# Sheet_1.net
KiCad netlist of a schematic drawn in Altium Designer
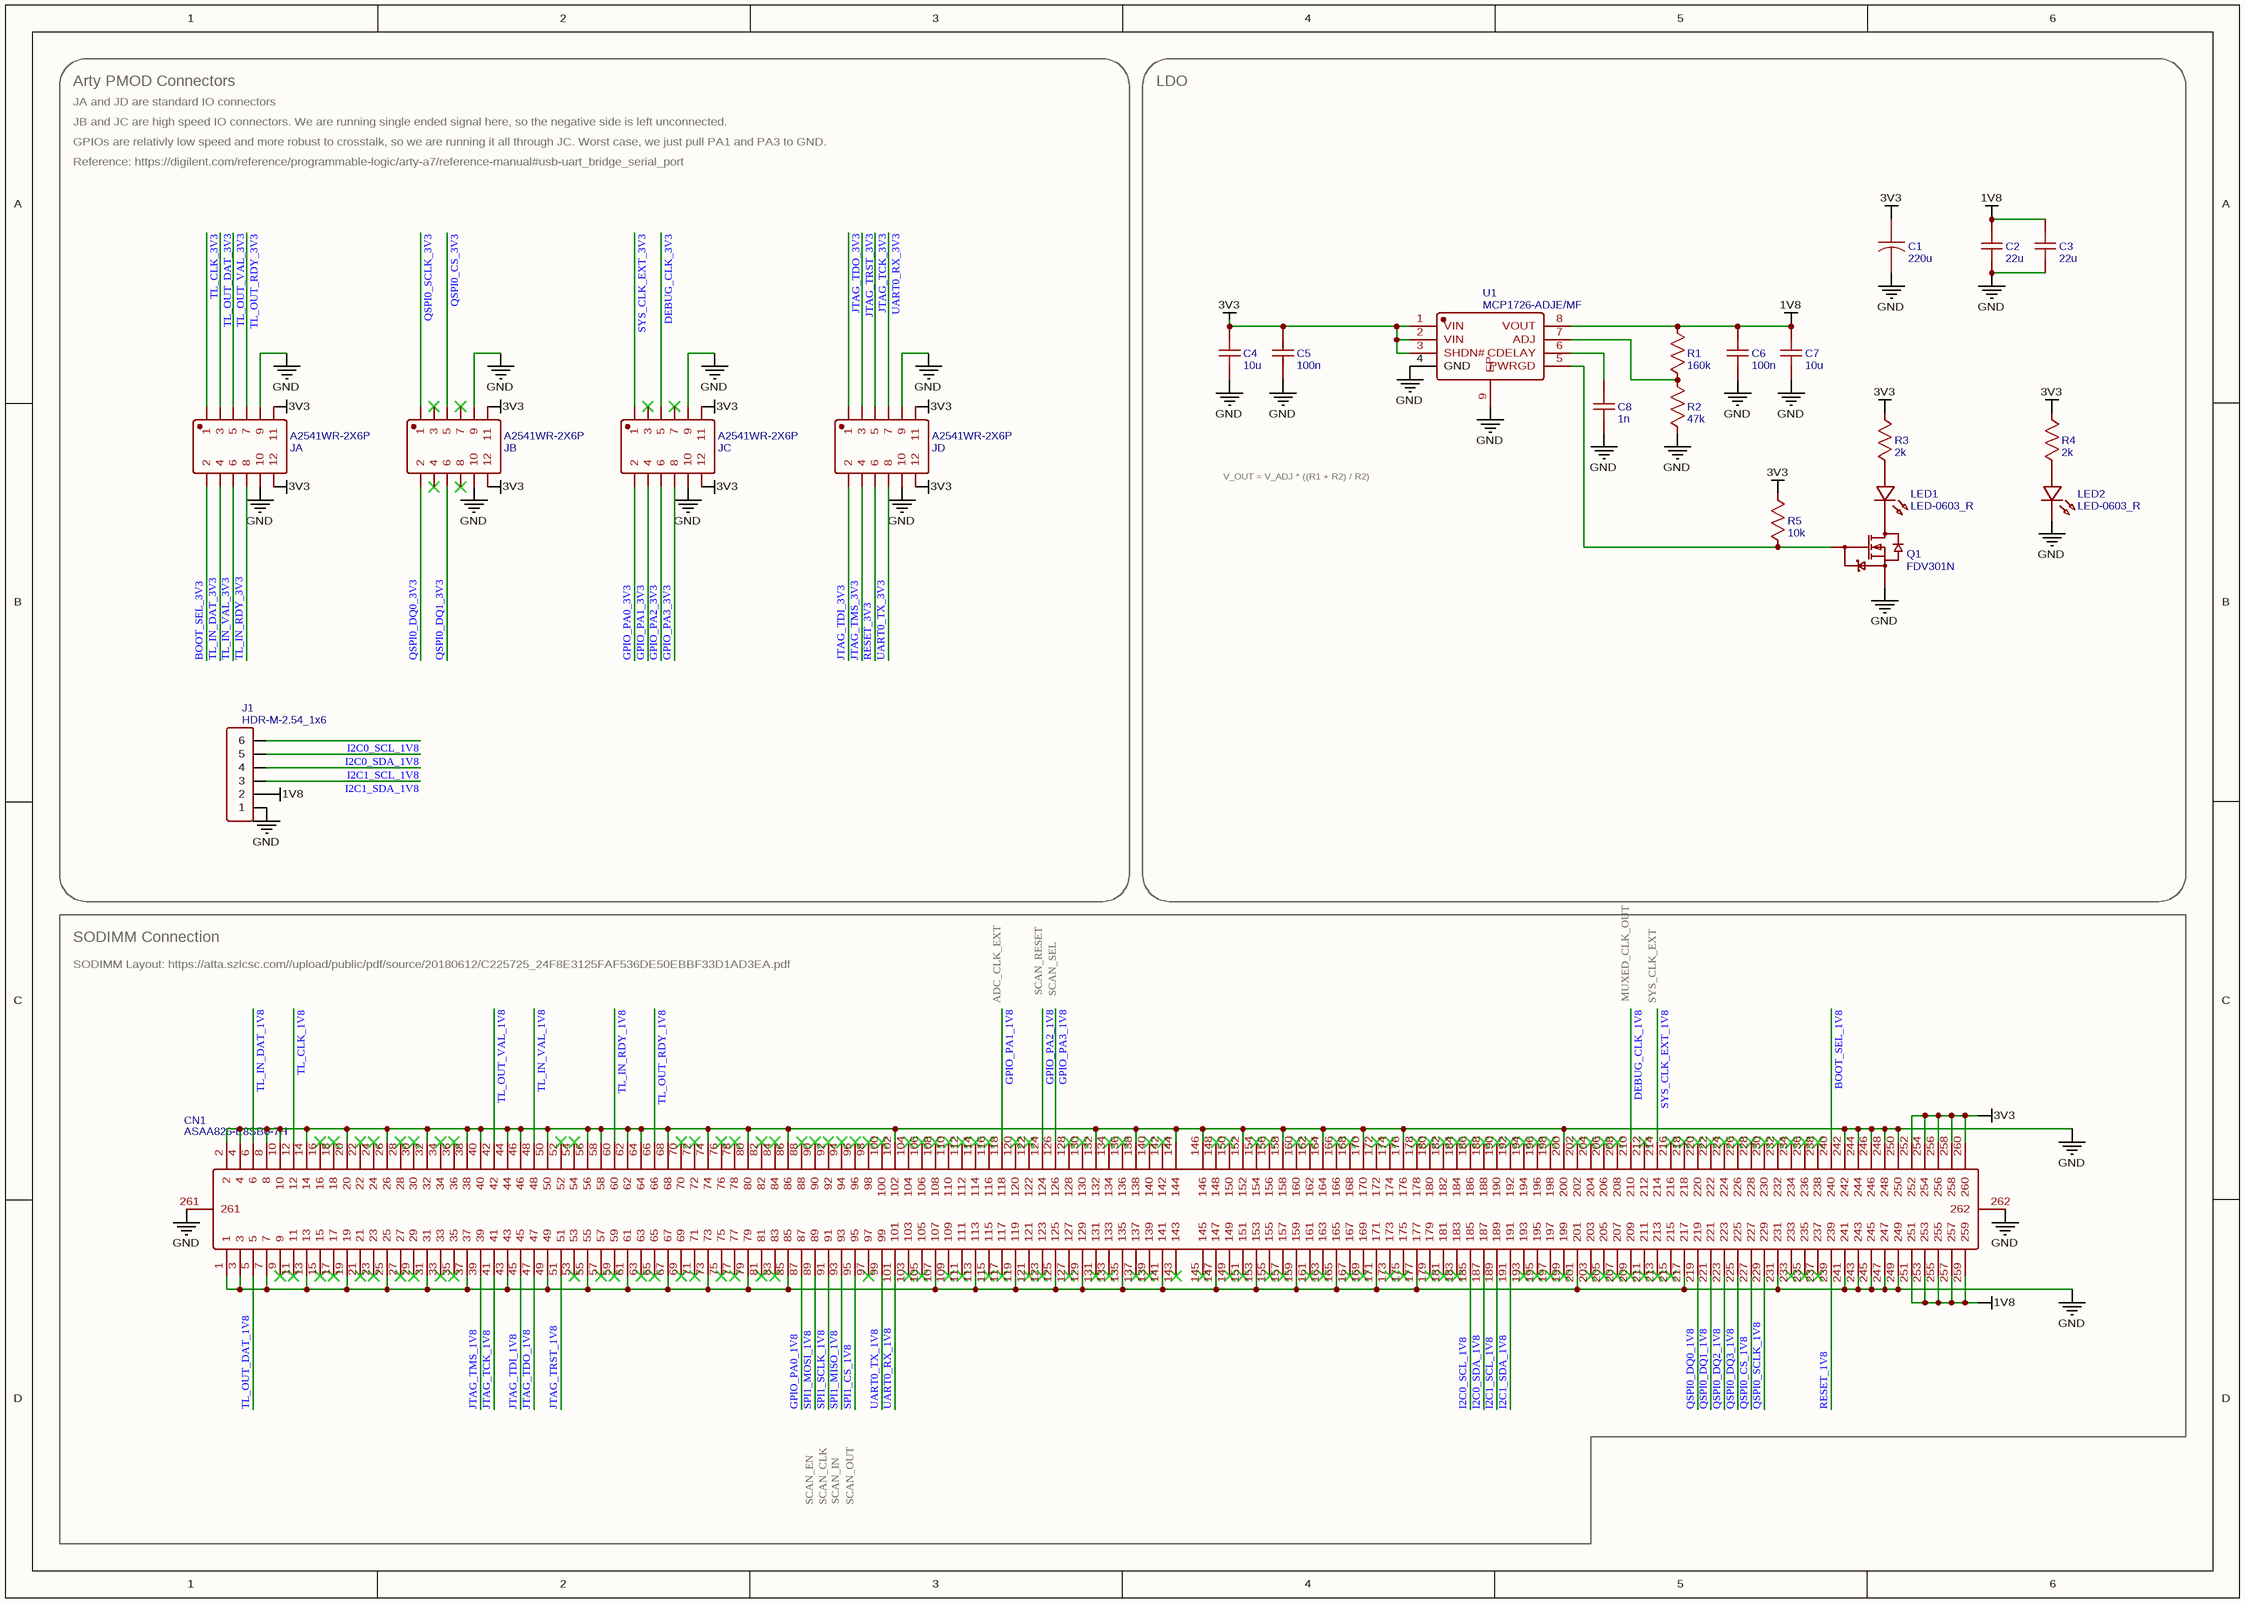
[diagram p0: Sheet_1.schdoc]

(export (version "E")
  (design (tool "Eeschema 10.0.6"))
  (components
    (comp (ref "C1")
      (value "220u")
      (footprint "CAPPR5.0-D6.3_L6.6_W6.6")
      (fields
        (field (name "BOM_SUPPLIER PART") "C131157")
        (field (name "BOM_MANUFACTURER PART") "CK1A221M-CRE54")
      )
      (libsource (lib "altium-import") (part "root_3_220u_"))
    )
    (comp (ref "C2")
      (value "22u")
      (footprint "CAPA-1206")
      (fields
        (field (name "BOM_SUPPLIER PART") "C12891")
        (field (name "BOM_MANUFACTURER PART") "CL31A226KAHNNNE")
      )
      (libsource (lib "altium-import") (part "root_1_22u_"))
    )
    (comp (ref "C3")
      (value "22u")
      (footprint "CAPA-1206")
      (fields
        (field (name "BOM_SUPPLIER PART") "C12891")
        (field (name "BOM_MANUFACTURER PART") "CL31A226KAHNNNE")
      )
      (libsource (lib "altium-import") (part "root_1_22u_"))
    )
    (comp (ref "C4")
      (value "10u")
      (footprint "CAPA-0402")
      (fields
        (field (name "BOM_SUPPLIER PART") "C87148")
        (field (name "BOM_MANUFACTURER PART") "JMK105CBJ106MV-F")
      )
      (libsource (lib "altium-import") (part "root_1_10u_"))
    )
    (comp (ref "C5")
      (value "100n")
      (footprint "CAPA-0402")
      (fields
        (field (name "BOM_SUPPLIER PART") "C307331")
        (field (name "BOM_MANUFACTURER PART") "CL05B104KB54PNC")
      )
      (libsource (lib "altium-import") (part "root_1_100n_"))
    )
    (comp (ref "C6")
      (value "100n")
      (footprint "CAPA-0402")
      (fields
        (field (name "BOM_SUPPLIER PART") "C307331")
        (field (name "BOM_MANUFACTURER PART") "CL05B104KB54PNC")
      )
      (libsource (lib "altium-import") (part "root_1_100n_"))
    )
    (comp (ref "C7")
      (value "10u")
      (footprint "CAPA-0402")
      (fields
        (field (name "BOM_SUPPLIER PART") "C87148")
        (field (name "BOM_MANUFACTURER PART") "JMK105CBJ106MV-F")
      )
      (libsource (lib "altium-import") (part "root_1_10u_"))
    )
    (comp (ref "C8")
      (value "1n")
      (footprint "CAPA-0402")
      (fields
        (field (name "BOM_SUPPLIER PART") "C113780")
        (field (name "BOM_MANUFACTURER PART") "CC0402JRNPO9BN102")
      )
      (libsource (lib "altium-import") (part "root_1_1n_"))
    )
    (comp (ref "CN1")
      (value "ASAA826-E8SB0-7H")
      (footprint "CONN-SMD_ASAA826-E8SB0-7H")
      (fields (field (name "BOM_SUPPLIER PART") "C2761395"))
      (libsource (lib "altium-import") (part "root_0_ASAA826-E8SB0-7H_"))
    )
    (comp (ref "J1")
      (value "HDR-M-2.54_1x6")
      (footprint "HDR-M-2.54_1X6")
      (fields (field (name "BOM_SUPPLIER PART") "C190819") (field (name "CONTRIBUTOR") "LCEDA_Lib"))
      (libsource (lib "altium-import") (part "root_2_HDR-M-2.54_1x6_"))
    )
    (comp (ref "JA")
      (value "A2541WR-2X6P")
      (footprint "CONN-TH_A2541WR-2X6P")
      (fields
        (field (name "BOM_SUPPLIER PART") "C239337")
        (field (name "BOM_MANUFACTURER PART") "A2541WR-2x6P")
      )
      (libsource (lib "altium-import") (part "root_1_A2541WR-2X6P_"))
    )
    (comp (ref "JB")
      (value "A2541WR-2X6P")
      (footprint "CONN-TH_A2541WR-2X6P")
      (fields
        (field (name "BOM_SUPPLIER PART") "C239337")
        (field (name "BOM_MANUFACTURER PART") "A2541WR-2x6P")
      )
      (libsource (lib "altium-import") (part "root_1_A2541WR-2X6P_"))
    )
    (comp (ref "JC")
      (value "A2541WR-2X6P")
      (footprint "CONN-TH_A2541WR-2X6P")
      (fields
        (field (name "BOM_SUPPLIER PART") "C239337")
        (field (name "BOM_MANUFACTURER PART") "A2541WR-2x6P")
      )
      (libsource (lib "altium-import") (part "root_1_A2541WR-2X6P_"))
    )
    (comp (ref "JD")
      (value "A2541WR-2X6P")
      (footprint "CONN-TH_A2541WR-2X6P")
      (fields
        (field (name "BOM_SUPPLIER PART") "C239337")
        (field (name "BOM_MANUFACTURER PART") "A2541WR-2x6P")
      )
      (libsource (lib "altium-import") (part "root_1_A2541WR-2X6P_"))
    )
    (comp (ref "LED1")
      (value "LED-0603_R")
      (footprint "LED-0603")
      (fields
        (field (name "BOM_MANUFACTURER PART") "19-217/R6C-AL1M2VY/3T")
        (field (name "BOM_SUPPLIER PART") "C72044")
        (field (name "CONTRIBUTOR") "LCEDA_01")
      )
      (libsource (lib "altium-import") (part "root_3_LED-0603_R_"))
    )
    (comp (ref "LED2")
      (value "LED-0603_R")
      (footprint "LED-0603")
      (fields
        (field (name "BOM_MANUFACTURER PART") "19-217/R6C-AL1M2VY/3T")
        (field (name "BOM_SUPPLIER PART") "C72044")
        (field (name "CONTRIBUTOR") "LCEDA_01")
      )
      (libsource (lib "altium-import") (part "root_3_LED-0603_R_"))
    )
    (comp (ref "Q1")
      (value "FDV301N")
      (footprint "SOT-23_L2.9-W1.3-P1.90-LS2.4-BR")
      (fields (field (name "BOM_SUPPLIER PART") "C15310"))
      (libsource (lib "altium-import") (part "root_0_FDV301N_"))
    )
    (comp (ref "R1")
      (value "160k")
      (footprint "RES-0402")
      (fields
        (field (name "BOM_SUPPLIER PART") "C25757")
        (field (name "BOM_MANUFACTURER PART") "0402WGF1603TCE")
      )
      (libsource (lib "altium-import") (part "root_1_160k_"))
    )
    (comp (ref "R2")
      (value "47k")
      (footprint "RES-0402")
      (fields
        (field (name "BOM_SUPPLIER PART") "C25792")
        (field (name "BOM_MANUFACTURER PART") "0402WGF4702TCE")
      )
      (libsource (lib "altium-import") (part "root_1_47k_"))
    )
    (comp (ref "R3")
      (value "2k")
      (footprint "RES-0402")
      (fields
        (field (name "BOM_SUPPLIER PART") "C4109")
        (field (name "BOM_MANUFACTURER PART") "0402WGF2001TCE")
      )
      (libsource (lib "altium-import") (part "root_1_2k_"))
    )
    (comp (ref "R4")
      (value "2k")
      (footprint "RES-0402")
      (fields
        (field (name "BOM_SUPPLIER PART") "C4109")
        (field (name "BOM_MANUFACTURER PART") "0402WGF2001TCE")
      )
      (libsource (lib "altium-import") (part "root_1_2k_"))
    )
    (comp (ref "R5")
      (value "10k")
      (footprint "RES-0402")
      (fields
        (field (name "BOM_SUPPLIER PART") "C25744")
        (field (name "BOM_MANUFACTURER PART") "0402WGF1002TCE")
      )
      (libsource (lib "altium-import") (part "root_1_10k_"))
    )
    (comp (ref "U1")
      (value "MCP1726-ADJE/MF")
      (footprint "TDFN-8_L3.0-W3.0-P0.65-BL-EP")
      (fields (field (name "BOM_SUPPLIER PART") "C184287"))
      (libsource (lib "altium-import") (part "root_0_MCP1726-ADJE/MF_"))
    )
  )
  (nets
    (net (code "1") (name "/BOOT_SEL_1V8") (class "Default")
      (node (ref "CN1") (pin "240") (pinfunction "240_240") (pintype "passive"))
    )
    (net (code "2") (name "/BOOT_SEL_3V3") (class "Default")
      (node (ref "JA") (pin "2") (pinfunction "2_2") (pintype "passive"))
    )
    (net (code "3") (name "/DEBUG_CLK_1V8") (class "Default")
      (node (ref "CN1") (pin "210") (pinfunction "210_210") (pintype "passive"))
    )
    (net (code "4") (name "/DEBUG_CLK_3V3") (class "Default")
      (node (ref "JC") (pin "5") (pinfunction "5_5") (pintype "passive"))
    )
    (net (code "5") (name "/GPIO_PA0_1V8") (class "Default")
      (node (ref "CN1") (pin "87") (pinfunction "87_87") (pintype "passive"))
    )
    (net (code "6") (name "/GPIO_PA0_3V3") (class "Default")
      (node (ref "JC") (pin "2") (pinfunction "2_2") (pintype "passive"))
    )
    (net (code "7") (name "/GPIO_PA1_1V8") (class "Default")
      (node (ref "CN1") (pin "118") (pinfunction "118_118") (pintype "passive"))
    )
    (net (code "8") (name "/GPIO_PA1_3V3") (class "Default")
      (node (ref "JC") (pin "4") (pinfunction "4_4") (pintype "passive"))
    )
    (net (code "9") (name "/GPIO_PA2_1V8") (class "Default")
      (node (ref "CN1") (pin "124") (pinfunction "124_124") (pintype "passive"))
    )
    (net (code "10") (name "/GPIO_PA2_3V3") (class "Default")
      (node (ref "JC") (pin "6") (pinfunction "6_6") (pintype "passive"))
    )
    (net (code "11") (name "/GPIO_PA3_1V8") (class "Default")
      (node (ref "CN1") (pin "126") (pinfunction "126_126") (pintype "passive"))
    )
    (net (code "12") (name "/GPIO_PA3_3V3") (class "Default")
      (node (ref "JC") (pin "8") (pinfunction "8_8") (pintype "passive"))
    )
    (net (code "13") (name "/I2C0_SCL_1V8") (class "Default")
      (node (ref "CN1") (pin "185") (pinfunction "185_185") (pintype "passive"))
      (node (ref "J1") (pin "6") (pinfunction "6_6") (pintype "passive"))
    )
    (net (code "14") (name "/I2C0_SDA_1V8") (class "Default")
      (node (ref "CN1") (pin "187") (pinfunction "187_187") (pintype "passive"))
      (node (ref "J1") (pin "5") (pinfunction "5_5") (pintype "passive"))
    )
    (net (code "15") (name "/I2C1_SCL_1V8") (class "Default")
      (node (ref "CN1") (pin "189") (pinfunction "189_189") (pintype "passive"))
      (node (ref "J1") (pin "4") (pinfunction "4_4") (pintype "passive"))
    )
    (net (code "16") (name "/I2C1_SDA_1V8") (class "Default")
      (node (ref "CN1") (pin "191") (pinfunction "191_191") (pintype "passive"))
      (node (ref "J1") (pin "3") (pinfunction "3_3") (pintype "passive"))
    )
    (net (code "17") (name "/JTAG_TCK_1V8") (class "Default")
      (node (ref "CN1") (pin "41") (pinfunction "41_41") (pintype "passive"))
    )
    (net (code "18") (name "/JTAG_TCK_3V3") (class "Default")
      (node (ref "JD") (pin "5") (pinfunction "5_5") (pintype "passive"))
    )
    (net (code "19") (name "/JTAG_TDI_1V8") (class "Default")
      (node (ref "CN1") (pin "45") (pinfunction "45_45") (pintype "passive"))
    )
    (net (code "20") (name "/JTAG_TDI_3V3") (class "Default")
      (node (ref "JD") (pin "2") (pinfunction "2_2") (pintype "passive"))
    )
    (net (code "21") (name "/JTAG_TDO_1V8") (class "Default")
      (node (ref "CN1") (pin "47") (pinfunction "47_47") (pintype "passive"))
    )
    (net (code "22") (name "/JTAG_TDO_3V3") (class "Default")
      (node (ref "JD") (pin "1") (pinfunction "1_1") (pintype "passive"))
    )
    (net (code "23") (name "/JTAG_TMS_1V8") (class "Default")
      (node (ref "CN1") (pin "39") (pinfunction "39_39") (pintype "passive"))
    )
    (net (code "24") (name "/JTAG_TMS_3V3") (class "Default")
      (node (ref "JD") (pin "4") (pinfunction "4_4") (pintype "passive"))
    )
    (net (code "25") (name "/JTAG_TRST_1V8") (class "Default")
      (node (ref "CN1") (pin "51") (pinfunction "51_51") (pintype "passive"))
    )
    (net (code "26") (name "/JTAG_TRST_3V3") (class "Default")
      (node (ref "JD") (pin "3") (pinfunction "3_3") (pintype "passive"))
    )
    (net (code "27") (name "/QSPI0_CS_1V8") (class "Default")
      (node (ref "CN1") (pin "227") (pinfunction "227_227") (pintype "passive"))
    )
    (net (code "28") (name "/QSPI0_CS_3V3") (class "Default")
      (node (ref "JB") (pin "5") (pinfunction "5_5") (pintype "passive"))
    )
    (net (code "29") (name "/QSPI0_DQ0_1V8") (class "Default")
      (node (ref "CN1") (pin "219") (pinfunction "219_219") (pintype "passive"))
    )
    (net (code "30") (name "/QSPI0_DQ0_3V3") (class "Default")
      (node (ref "JB") (pin "2") (pinfunction "2_2") (pintype "passive"))
    )
    (net (code "31") (name "/QSPI0_DQ1_1V8") (class "Default")
      (node (ref "CN1") (pin "221") (pinfunction "221_221") (pintype "passive"))
    )
    (net (code "32") (name "/QSPI0_DQ1_3V3") (class "Default")
      (node (ref "JB") (pin "6") (pinfunction "6_6") (pintype "passive"))
    )
    (net (code "33") (name "/QSPI0_DQ2_1V8") (class "Default")
      (node (ref "CN1") (pin "223") (pinfunction "223_223") (pintype "passive"))
    )
    (net (code "34") (name "/QSPI0_DQ3_1V8") (class "Default")
      (node (ref "CN1") (pin "225") (pinfunction "225_225") (pintype "passive"))
    )
    (net (code "35") (name "/QSPI0_SCLK_1V8") (class "Default")
      (node (ref "CN1") (pin "229") (pinfunction "229_229") (pintype "passive"))
    )
    (net (code "36") (name "/QSPI0_SCLK_3V3") (class "Default")
      (node (ref "JB") (pin "1") (pinfunction "1_1") (pintype "passive"))
    )
    (net (code "37") (name "/RESET_1V8") (class "Default")
      (node (ref "CN1") (pin "239") (pinfunction "239_239") (pintype "passive"))
    )
    (net (code "38") (name "/RESET_3V3") (class "Default")
      (node (ref "JD") (pin "6") (pinfunction "6_6") (pintype "passive"))
    )
    (net (code "39") (name "/SPI1_CS_1V8") (class "Default")
      (node (ref "CN1") (pin "95") (pinfunction "95_95") (pintype "passive"))
    )
    (net (code "40") (name "/SPI1_MISO_1V8") (class "Default")
      (node (ref "CN1") (pin "93") (pinfunction "93_93") (pintype "passive"))
    )
    (net (code "41") (name "/SPI1_MOSI_1V8") (class "Default")
      (node (ref "CN1") (pin "89") (pinfunction "89_89") (pintype "passive"))
    )
    (net (code "42") (name "/SPI1_SCLK_1V8") (class "Default")
      (node (ref "CN1") (pin "91") (pinfunction "91_91") (pintype "passive"))
    )
    (net (code "43") (name "/SYS_CLK_EXT_1V8") (class "Default")
      (node (ref "CN1") (pin "214") (pinfunction "214_214") (pintype "passive"))
    )
    (net (code "44") (name "/SYS_CLK_EXT_3V3") (class "Default")
      (node (ref "JC") (pin "1") (pinfunction "1_1") (pintype "passive"))
    )
    (net (code "45") (name "/TL_CLK_1V8") (class "Default")
      (node (ref "CN1") (pin "12") (pinfunction "12_12") (pintype "passive"))
    )
    (net (code "46") (name "/TL_CLK_3V3") (class "Default")
      (node (ref "JA") (pin "1") (pinfunction "1_1") (pintype "passive"))
    )
    (net (code "47") (name "/TL_IN_DAT_1V8") (class "Default")
      (node (ref "CN1") (pin "6") (pinfunction "6_6") (pintype "passive"))
    )
    (net (code "48") (name "/TL_IN_DAT_3V3") (class "Default")
      (node (ref "JA") (pin "4") (pinfunction "4_4") (pintype "passive"))
    )
    (net (code "49") (name "/TL_IN_RDY_1V8") (class "Default")
      (node (ref "CN1") (pin "60") (pinfunction "60_60") (pintype "passive"))
    )
    (net (code "50") (name "/TL_IN_RDY_3V3") (class "Default")
      (node (ref "JA") (pin "8") (pinfunction "8_8") (pintype "passive"))
    )
    (net (code "51") (name "/TL_IN_VAL_1V8") (class "Default")
      (node (ref "CN1") (pin "48") (pinfunction "48_48") (pintype "passive"))
    )
    (net (code "52") (name "/TL_IN_VAL_3V3") (class "Default")
      (node (ref "JA") (pin "6") (pinfunction "6_6") (pintype "passive"))
    )
    (net (code "53") (name "/TL_OUT_DAT_1V8") (class "Default")
      (node (ref "CN1") (pin "5") (pinfunction "5_5") (pintype "passive"))
    )
    (net (code "54") (name "/TL_OUT_DAT_3V3") (class "Default")
      (node (ref "JA") (pin "3") (pinfunction "3_3") (pintype "passive"))
    )
    (net (code "55") (name "/TL_OUT_RDY_1V8") (class "Default")
      (node (ref "CN1") (pin "66") (pinfunction "66_66") (pintype "passive"))
    )
    (net (code "56") (name "/TL_OUT_RDY_3V3") (class "Default")
      (node (ref "JA") (pin "7") (pinfunction "7_7") (pintype "passive"))
    )
    (net (code "57") (name "/TL_OUT_VAL_1V8") (class "Default")
      (node (ref "CN1") (pin "42") (pinfunction "42_42") (pintype "passive"))
    )
    (net (code "58") (name "/TL_OUT_VAL_3V3") (class "Default")
      (node (ref "JA") (pin "5") (pinfunction "5_5") (pintype "passive"))
    )
    (net (code "59") (name "/UART0_RX_1V8") (class "Default")
      (node (ref "CN1") (pin "101") (pinfunction "101_101") (pintype "passive"))
    )
    (net (code "60") (name "/UART0_RX_3V3") (class "Default")
      (node (ref "JD") (pin "7") (pinfunction "7_7") (pintype "passive"))
    )
    (net (code "61") (name "/UART0_TX_1V8") (class "Default")
      (node (ref "CN1") (pin "99") (pinfunction "99_99") (pintype "passive"))
    )
    (net (code "62") (name "/UART0_TX_3V3") (class "Default")
      (node (ref "JD") (pin "8") (pinfunction "8_8") (pintype "passive"))
    )
    (net (code "63") (name "1V8") (class "Default")
      (node (ref "C2") (pin "2") (pinfunction "2_2") (pintype "passive"))
      (node (ref "C3") (pin "2") (pinfunction "2_2") (pintype "passive"))
      (node (ref "C6") (pin "2") (pinfunction "2_2") (pintype "passive"))
      (node (ref "C7") (pin "2") (pinfunction "2_2") (pintype "passive"))
      (node (ref "CN1") (pin "251") (pinfunction "251_251") (pintype "passive"))
      (node (ref "CN1") (pin "253") (pinfunction "253_253") (pintype "passive"))
      (node (ref "CN1") (pin "255") (pinfunction "255_255") (pintype "passive"))
      (node (ref "CN1") (pin "257") (pinfunction "257_257") (pintype "passive"))
      (node (ref "CN1") (pin "259") (pinfunction "259_259") (pintype "passive"))
      (node (ref "J1") (pin "2") (pinfunction "2_2") (pintype "passive"))
      (node (ref "R1") (pin "2") (pinfunction "2_2") (pintype "passive"))
      (node (ref "U1") (pin "8") (pinfunction "VOUT_8") (pintype "passive"))
    )
    (net (code "64") (name "3V3") (class "Default")
      (node (ref "C1") (pin "1") (pinfunction "1_1") (pintype "passive"))
      (node (ref "C4") (pin "2") (pinfunction "2_2") (pintype "passive"))
      (node (ref "C5") (pin "2") (pinfunction "2_2") (pintype "passive"))
      (node (ref "CN1") (pin "252") (pinfunction "252_252") (pintype "passive"))
      (node (ref "CN1") (pin "254") (pinfunction "254_254") (pintype "passive"))
      (node (ref "CN1") (pin "256") (pinfunction "256_256") (pintype "passive"))
      (node (ref "CN1") (pin "258") (pinfunction "258_258") (pintype "passive"))
      (node (ref "CN1") (pin "260") (pinfunction "260_260") (pintype "passive"))
      (node (ref "JA") (pin "11") (pinfunction "11_11") (pintype "passive"))
      (node (ref "JA") (pin "12") (pinfunction "12_12") (pintype "passive"))
      (node (ref "JB") (pin "11") (pinfunction "11_11") (pintype "passive"))
      (node (ref "JB") (pin "12") (pinfunction "12_12") (pintype "passive"))
      (node (ref "JC") (pin "11") (pinfunction "11_11") (pintype "passive"))
      (node (ref "JC") (pin "12") (pinfunction "12_12") (pintype "passive"))
      (node (ref "JD") (pin "11") (pinfunction "11_11") (pintype "passive"))
      (node (ref "JD") (pin "12") (pinfunction "12_12") (pintype "passive"))
      (node (ref "R3") (pin "2") (pinfunction "2_2") (pintype "passive"))
      (node (ref "R4") (pin "2") (pinfunction "2_2") (pintype "passive"))
      (node (ref "R5") (pin "2") (pinfunction "2_2") (pintype "passive"))
      (node (ref "U1") (pin "1") (pinfunction "VIN_1") (pintype "passive"))
      (node (ref "U1") (pin "2") (pinfunction "VIN_2") (pintype "passive"))
      (node (ref "U1") (pin "3") (pinfunction "SHDN#_3") (pintype "passive"))
    )
    (net (code "65") (name "GND") (class "Default")
      (node (ref "C1") (pin "2") (pinfunction "2_2") (pintype "passive"))
      (node (ref "C2") (pin "1") (pinfunction "1_1") (pintype "passive"))
      (node (ref "C3") (pin "1") (pinfunction "1_1") (pintype "passive"))
      (node (ref "C4") (pin "1") (pinfunction "1_1") (pintype "passive"))
      (node (ref "C5") (pin "1") (pinfunction "1_1") (pintype "passive"))
      (node (ref "C6") (pin "1") (pinfunction "1_1") (pintype "passive"))
      (node (ref "C7") (pin "1") (pinfunction "1_1") (pintype "passive"))
      (node (ref "C8") (pin "1") (pinfunction "1_1") (pintype "passive"))
      (node (ref "CN1") (pin "1") (pinfunction "1_1") (pintype "passive"))
      (node (ref "CN1") (pin "10") (pinfunction "10_10") (pintype "passive"))
      (node (ref "CN1") (pin "102") (pinfunction "102_102") (pintype "passive"))
      (node (ref "CN1") (pin "107") (pinfunction "107_107") (pintype "passive"))
      (node (ref "CN1") (pin "113") (pinfunction "113_113") (pintype "passive"))
      (node (ref "CN1") (pin "119") (pinfunction "119_119") (pintype "passive"))
      (node (ref "CN1") (pin "125") (pinfunction "125_125") (pintype "passive"))
      (node (ref "CN1") (pin "129") (pinfunction "129_129") (pintype "passive"))
      (node (ref "CN1") (pin "13") (pinfunction "13_13") (pintype "passive"))
      (node (ref "CN1") (pin "132") (pinfunction "132_132") (pintype "passive"))
      (node (ref "CN1") (pin "135") (pinfunction "135_135") (pintype "passive"))
      (node (ref "CN1") (pin "138") (pinfunction "138_138") (pintype "passive"))
      (node (ref "CN1") (pin "14") (pinfunction "14_14") (pintype "passive"))
      (node (ref "CN1") (pin "141") (pinfunction "141_141") (pintype "passive"))
      (node (ref "CN1") (pin "144") (pinfunction "144_144") (pintype "passive"))
      (node (ref "CN1") (pin "146") (pinfunction "146_146") (pintype "passive"))
      (node (ref "CN1") (pin "147") (pinfunction "147_147") (pintype "passive"))
      (node (ref "CN1") (pin "152") (pinfunction "152_152") (pintype "passive"))
      (node (ref "CN1") (pin "153") (pinfunction "153_153") (pintype "passive"))
      (node (ref "CN1") (pin "158") (pinfunction "158_158") (pintype "passive"))
      (node (ref "CN1") (pin "159") (pinfunction "159_159") (pintype "passive"))
      (node (ref "CN1") (pin "164") (pinfunction "164_164") (pintype "passive"))
      (node (ref "CN1") (pin "165") (pinfunction "165_165") (pintype "passive"))
      (node (ref "CN1") (pin "170") (pinfunction "170_170") (pintype "passive"))
      (node (ref "CN1") (pin "171") (pinfunction "171_171") (pintype "passive"))
      (node (ref "CN1") (pin "176") (pinfunction "176_176") (pintype "passive"))
      (node (ref "CN1") (pin "177") (pinfunction "177_177") (pintype "passive"))
      (node (ref "CN1") (pin "19") (pinfunction "19_19") (pintype "passive"))
      (node (ref "CN1") (pin "2") (pinfunction "2_2") (pintype "passive"))
      (node (ref "CN1") (pin "20") (pinfunction "20_20") (pintype "passive"))
      (node (ref "CN1") (pin "200") (pinfunction "200_200") (pintype "passive"))
      (node (ref "CN1") (pin "201") (pinfunction "201_201") (pintype "passive"))
      (node (ref "CN1") (pin "217") (pinfunction "217_217") (pintype "passive"))
      (node (ref "CN1") (pin "231") (pinfunction "231_231") (pintype "passive"))
      (node (ref "CN1") (pin "241") (pinfunction "241_241") (pintype "passive"))
      (node (ref "CN1") (pin "242") (pinfunction "242_242") (pintype "passive"))
      (node (ref "CN1") (pin "243") (pinfunction "243_243") (pintype "passive"))
      (node (ref "CN1") (pin "244") (pinfunction "244_244") (pintype "passive"))
      (node (ref "CN1") (pin "245") (pinfunction "245_245") (pintype "passive"))
      (node (ref "CN1") (pin "246") (pinfunction "246_246") (pintype "passive"))
      (node (ref "CN1") (pin "247") (pinfunction "247_247") (pintype "passive"))
      (node (ref "CN1") (pin "248") (pinfunction "248_248") (pintype "passive"))
      (node (ref "CN1") (pin "249") (pinfunction "249_249") (pintype "passive"))
      (node (ref "CN1") (pin "25") (pinfunction "25_25") (pintype "passive"))
      (node (ref "CN1") (pin "250") (pinfunction "250_250") (pintype "passive"))
      (node (ref "CN1") (pin "26") (pinfunction "26_26") (pintype "passive"))
      (node (ref "CN1") (pin "261") (pinfunction "261_261") (pintype "passive"))
      (node (ref "CN1") (pin "262") (pinfunction "262_262") (pintype "passive"))
      (node (ref "CN1") (pin "3") (pinfunction "3_3") (pintype "passive"))
      (node (ref "CN1") (pin "31") (pinfunction "31_31") (pintype "passive"))
      (node (ref "CN1") (pin "32") (pinfunction "32_32") (pintype "passive"))
      (node (ref "CN1") (pin "37") (pinfunction "37_37") (pintype "passive"))
      (node (ref "CN1") (pin "38") (pinfunction "38_38") (pintype "passive"))
      (node (ref "CN1") (pin "4") (pinfunction "4_4") (pintype "passive"))
      (node (ref "CN1") (pin "40") (pinfunction "40_40") (pintype "passive"))
      (node (ref "CN1") (pin "43") (pinfunction "43_43") (pintype "passive"))
      (node (ref "CN1") (pin "44") (pinfunction "44_44") (pintype "passive"))
      (node (ref "CN1") (pin "46") (pinfunction "46_46") (pintype "passive"))
      (node (ref "CN1") (pin "49") (pinfunction "49_49") (pintype "passive"))
      (node (ref "CN1") (pin "50") (pinfunction "50_50") (pintype "passive"))
      (node (ref "CN1") (pin "55") (pinfunction "55_55") (pintype "passive"))
      (node (ref "CN1") (pin "56") (pinfunction "56_56") (pintype "passive"))
      (node (ref "CN1") (pin "58") (pinfunction "58_58") (pintype "passive"))
      (node (ref "CN1") (pin "61") (pinfunction "61_61") (pintype "passive"))
      (node (ref "CN1") (pin "62") (pinfunction "62_62") (pintype "passive"))
      (node (ref "CN1") (pin "64") (pinfunction "64_64") (pintype "passive"))
      (node (ref "CN1") (pin "67") (pinfunction "67_67") (pintype "passive"))
      (node (ref "CN1") (pin "68") (pinfunction "68_68") (pintype "passive"))
      (node (ref "CN1") (pin "7") (pinfunction "7_7") (pintype "passive"))
      (node (ref "CN1") (pin "73") (pinfunction "73_73") (pintype "passive"))
      (node (ref "CN1") (pin "74") (pinfunction "74_74") (pintype "passive"))
      (node (ref "CN1") (pin "79") (pinfunction "79_79") (pintype "passive"))
      (node (ref "CN1") (pin "8") (pinfunction "8_8") (pintype "passive"))
      (node (ref "CN1") (pin "80") (pinfunction "80_80") (pintype "passive"))
      (node (ref "CN1") (pin "85") (pinfunction "85_85") (pintype "passive"))
      (node (ref "CN1") (pin "86") (pinfunction "86_86") (pintype "passive"))
      (node (ref "J1") (pin "1") (pinfunction "1_1") (pintype "passive"))
      (node (ref "JA") (pin "10") (pinfunction "10_10") (pintype "passive"))
      (node (ref "JA") (pin "9") (pinfunction "9_9") (pintype "passive"))
      (node (ref "JB") (pin "10") (pinfunction "10_10") (pintype "passive"))
      (node (ref "JB") (pin "9") (pinfunction "9_9") (pintype "passive"))
      (node (ref "JC") (pin "10") (pinfunction "10_10") (pintype "passive"))
      (node (ref "JC") (pin "9") (pinfunction "9_9") (pintype "passive"))
      (node (ref "JD") (pin "10") (pinfunction "10_10") (pintype "passive"))
      (node (ref "JD") (pin "9") (pinfunction "9_9") (pintype "passive"))
      (node (ref "LED2") (pin "2") (pinfunction "2_2") (pintype "passive"))
      (node (ref "Q1") (pin "2") (pinfunction "S_2") (pintype "passive"))
      (node (ref "R2") (pin "1") (pinfunction "1_1") (pintype "passive"))
      (node (ref "U1") (pin "4") (pinfunction "GND_4") (pintype "passive"))
      (node (ref "U1") (pin "9") (pinfunction "EP_9") (pintype "passive"))
    )
    (net (code "66") (name "Net-(LED1-Pad1)") (class "Default")
      (node (ref "LED1") (pin "1") (pinfunction "1_1") (pintype "passive"))
      (node (ref "R3") (pin "1") (pinfunction "1_1") (pintype "passive"))
    )
    (net (code "67") (name "Net-(LED2-Pad1)") (class "Default")
      (node (ref "LED2") (pin "1") (pinfunction "1_1") (pintype "passive"))
      (node (ref "R4") (pin "1") (pinfunction "1_1") (pintype "passive"))
    )
    (net (code "68") (name "Net-(Q1-D)") (class "Default")
      (node (ref "LED1") (pin "2") (pinfunction "2_2") (pintype "passive"))
      (node (ref "Q1") (pin "3") (pinfunction "D_3") (pintype "passive"))
    )
    (net (code "69") (name "Net-(Q1-G)") (class "Default")
      (node (ref "Q1") (pin "1") (pinfunction "G_1") (pintype "passive"))
      (node (ref "R5") (pin "1") (pinfunction "1_1") (pintype "passive"))
      (node (ref "U1") (pin "5") (pinfunction "PWRGD_5") (pintype "passive"))
    )
    (net (code "70") (name "Net-(U1-ADJ)") (class "Default")
      (node (ref "R1") (pin "1") (pinfunction "1_1") (pintype "passive"))
      (node (ref "R2") (pin "2") (pinfunction "2_2") (pintype "passive"))
      (node (ref "U1") (pin "7") (pinfunction "ADJ_7") (pintype "passive"))
    )
    (net (code "71") (name "Net-(U1-CDELAY)") (class "Default")
      (node (ref "C8") (pin "2") (pinfunction "2_2") (pintype "passive"))
      (node (ref "U1") (pin "6") (pinfunction "CDELAY_6") (pintype "passive"))
    )
    (net (code "72") (name "unconnected-(CN1-Pad9)") (class "Default")
      (node (ref "CN1") (pin "9") (pinfunction "9_9") (pintype "passive+no_connect"))
    )
    (net (code "73") (name "unconnected-(CN1-Pad11)") (class "Default")
      (node (ref "CN1") (pin "11") (pinfunction "11_11") (pintype "passive+no_connect"))
    )
    (net (code "74") (name "unconnected-(CN1-Pad15)") (class "Default")
      (node (ref "CN1") (pin "15") (pinfunction "15_15") (pintype "passive+no_connect"))
    )
    (net (code "75") (name "unconnected-(CN1-Pad16)") (class "Default")
      (node (ref "CN1") (pin "16") (pinfunction "16_16") (pintype "passive+no_connect"))
    )
    (net (code "76") (name "unconnected-(CN1-Pad17)") (class "Default")
      (node (ref "CN1") (pin "17") (pinfunction "17_17") (pintype "passive+no_connect"))
    )
    (net (code "77") (name "unconnected-(CN1-Pad18)") (class "Default")
      (node (ref "CN1") (pin "18") (pinfunction "18_18") (pintype "passive+no_connect"))
    )
    (net (code "78") (name "unconnected-(CN1-Pad21)") (class "Default")
      (node (ref "CN1") (pin "21") (pinfunction "21_21") (pintype "passive+no_connect"))
    )
    (net (code "79") (name "unconnected-(CN1-Pad22)") (class "Default")
      (node (ref "CN1") (pin "22") (pinfunction "22_22") (pintype "passive+no_connect"))
    )
    (net (code "80") (name "unconnected-(CN1-Pad23)") (class "Default")
      (node (ref "CN1") (pin "23") (pinfunction "23_23") (pintype "passive+no_connect"))
    )
    (net (code "81") (name "unconnected-(CN1-Pad24)") (class "Default")
      (node (ref "CN1") (pin "24") (pinfunction "24_24") (pintype "passive+no_connect"))
    )
    (net (code "82") (name "unconnected-(CN1-Pad27)") (class "Default")
      (node (ref "CN1") (pin "27") (pinfunction "27_27") (pintype "passive+no_connect"))
    )
    (net (code "83") (name "unconnected-(CN1-Pad28)") (class "Default")
      (node (ref "CN1") (pin "28") (pinfunction "28_28") (pintype "passive+no_connect"))
    )
    (net (code "84") (name "unconnected-(CN1-Pad29)") (class "Default")
      (node (ref "CN1") (pin "29") (pinfunction "29_29") (pintype "passive+no_connect"))
    )
    (net (code "85") (name "unconnected-(CN1-Pad30)") (class "Default")
      (node (ref "CN1") (pin "30") (pinfunction "30_30") (pintype "passive+no_connect"))
    )
    (net (code "86") (name "unconnected-(CN1-Pad33)") (class "Default")
      (node (ref "CN1") (pin "33") (pinfunction "33_33") (pintype "passive+no_connect"))
    )
    (net (code "87") (name "unconnected-(CN1-Pad34)") (class "Default")
      (node (ref "CN1") (pin "34") (pinfunction "34_34") (pintype "passive+no_connect"))
    )
    (net (code "88") (name "unconnected-(CN1-Pad35)") (class "Default")
      (node (ref "CN1") (pin "35") (pinfunction "35_35") (pintype "passive+no_connect"))
    )
    (net (code "89") (name "unconnected-(CN1-Pad36)") (class "Default")
      (node (ref "CN1") (pin "36") (pinfunction "36_36") (pintype "passive+no_connect"))
    )
    (net (code "90") (name "unconnected-(CN1-Pad52)") (class "Default")
      (node (ref "CN1") (pin "52") (pinfunction "52_52") (pintype "passive+no_connect"))
    )
    (net (code "91") (name "unconnected-(CN1-Pad53)") (class "Default")
      (node (ref "CN1") (pin "53") (pinfunction "53_53") (pintype "passive+no_connect"))
    )
    (net (code "92") (name "unconnected-(CN1-Pad54)") (class "Default")
      (node (ref "CN1") (pin "54") (pinfunction "54_54") (pintype "passive+no_connect"))
    )
    (net (code "93") (name "unconnected-(CN1-Pad57)") (class "Default")
      (node (ref "CN1") (pin "57") (pinfunction "57_57") (pintype "passive+no_connect"))
    )
    (net (code "94") (name "unconnected-(CN1-Pad59)") (class "Default")
      (node (ref "CN1") (pin "59") (pinfunction "59_59") (pintype "passive+no_connect"))
    )
    (net (code "95") (name "unconnected-(CN1-Pad63)") (class "Default")
      (node (ref "CN1") (pin "63") (pinfunction "63_63") (pintype "passive+no_connect"))
    )
    (net (code "96") (name "unconnected-(CN1-Pad65)") (class "Default")
      (node (ref "CN1") (pin "65") (pinfunction "65_65") (pintype "passive+no_connect"))
    )
    (net (code "97") (name "unconnected-(CN1-Pad69)") (class "Default")
      (node (ref "CN1") (pin "69") (pinfunction "69_69") (pintype "passive+no_connect"))
    )
    (net (code "98") (name "unconnected-(CN1-Pad70)") (class "Default")
      (node (ref "CN1") (pin "70") (pinfunction "70_70") (pintype "passive+no_connect"))
    )
    (net (code "99") (name "unconnected-(CN1-Pad71)") (class "Default")
      (node (ref "CN1") (pin "71") (pinfunction "71_71") (pintype "passive+no_connect"))
    )
    (net (code "100") (name "unconnected-(CN1-Pad72)") (class "Default")
      (node (ref "CN1") (pin "72") (pinfunction "72_72") (pintype "passive+no_connect"))
    )
    (net (code "101") (name "unconnected-(CN1-Pad75)") (class "Default")
      (node (ref "CN1") (pin "75") (pinfunction "75_75") (pintype "passive+no_connect"))
    )
    (net (code "102") (name "unconnected-(CN1-Pad76)") (class "Default")
      (node (ref "CN1") (pin "76") (pinfunction "76_76") (pintype "passive+no_connect"))
    )
    (net (code "103") (name "unconnected-(CN1-Pad77)") (class "Default")
      (node (ref "CN1") (pin "77") (pinfunction "77_77") (pintype "passive+no_connect"))
    )
    (net (code "104") (name "unconnected-(CN1-Pad78)") (class "Default")
      (node (ref "CN1") (pin "78") (pinfunction "78_78") (pintype "passive+no_connect"))
    )
    (net (code "105") (name "unconnected-(CN1-Pad81)") (class "Default")
      (node (ref "CN1") (pin "81") (pinfunction "81_81") (pintype "passive+no_connect"))
    )
    (net (code "106") (name "unconnected-(CN1-Pad82)") (class "Default")
      (node (ref "CN1") (pin "82") (pinfunction "82_82") (pintype "passive+no_connect"))
    )
    (net (code "107") (name "unconnected-(CN1-Pad83)") (class "Default")
      (node (ref "CN1") (pin "83") (pinfunction "83_83") (pintype "passive+no_connect"))
    )
    (net (code "108") (name "unconnected-(CN1-Pad84)") (class "Default")
      (node (ref "CN1") (pin "84") (pinfunction "84_84") (pintype "passive+no_connect"))
    )
    (net (code "109") (name "unconnected-(CN1-Pad88)") (class "Default")
      (node (ref "CN1") (pin "88") (pinfunction "88_88") (pintype "passive+no_connect"))
    )
    (net (code "110") (name "unconnected-(CN1-Pad90)") (class "Default")
      (node (ref "CN1") (pin "90") (pinfunction "90_90") (pintype "passive+no_connect"))
    )
    (net (code "111") (name "unconnected-(CN1-Pad92)") (class "Default")
      (node (ref "CN1") (pin "92") (pinfunction "92_92") (pintype "passive+no_connect"))
    )
    (net (code "112") (name "unconnected-(CN1-Pad94)") (class "Default")
      (node (ref "CN1") (pin "94") (pinfunction "94_94") (pintype "passive+no_connect"))
    )
    (net (code "113") (name "unconnected-(CN1-Pad96)") (class "Default")
      (node (ref "CN1") (pin "96") (pinfunction "96_96") (pintype "passive+no_connect"))
    )
    (net (code "114") (name "unconnected-(CN1-Pad97)") (class "Default")
      (node (ref "CN1") (pin "97") (pinfunction "97_97") (pintype "passive+no_connect"))
    )
    (net (code "115") (name "unconnected-(CN1-Pad98)") (class "Default")
      (node (ref "CN1") (pin "98") (pinfunction "98_98") (pintype "passive+no_connect"))
    )
    (net (code "116") (name "unconnected-(CN1-Pad100)") (class "Default")
      (node (ref "CN1") (pin "100") (pinfunction "100_100") (pintype "passive+no_connect"))
    )
    (net (code "117") (name "unconnected-(CN1-Pad103)") (class "Default")
      (node (ref "CN1") (pin "103") (pinfunction "103_103") (pintype "passive+no_connect"))
    )
    (net (code "118") (name "unconnected-(CN1-Pad104)") (class "Default")
      (node (ref "CN1") (pin "104") (pinfunction "104_104") (pintype "passive+no_connect"))
    )
    (net (code "119") (name "unconnected-(CN1-Pad105)") (class "Default")
      (node (ref "CN1") (pin "105") (pinfunction "105_105") (pintype "passive+no_connect"))
    )
    (net (code "120") (name "unconnected-(CN1-Pad106)") (class "Default")
      (node (ref "CN1") (pin "106") (pinfunction "106_106") (pintype "passive+no_connect"))
    )
    (net (code "121") (name "unconnected-(CN1-Pad108)") (class "Default")
      (node (ref "CN1") (pin "108") (pinfunction "108_108") (pintype "passive+no_connect"))
    )
    (net (code "122") (name "unconnected-(CN1-Pad109)") (class "Default")
      (node (ref "CN1") (pin "109") (pinfunction "109_109") (pintype "passive+no_connect"))
    )
    (net (code "123") (name "unconnected-(CN1-Pad110)") (class "Default")
      (node (ref "CN1") (pin "110") (pinfunction "110_110") (pintype "passive+no_connect"))
    )
    (net (code "124") (name "unconnected-(CN1-Pad111)") (class "Default")
      (node (ref "CN1") (pin "111") (pinfunction "111_111") (pintype "passive+no_connect"))
    )
    (net (code "125") (name "unconnected-(CN1-Pad112)") (class "Default")
      (node (ref "CN1") (pin "112") (pinfunction "112_112") (pintype "passive+no_connect"))
    )
    (net (code "126") (name "unconnected-(CN1-Pad114)") (class "Default")
      (node (ref "CN1") (pin "114") (pinfunction "114_114") (pintype "passive+no_connect"))
    )
    (net (code "127") (name "unconnected-(CN1-Pad115)") (class "Default")
      (node (ref "CN1") (pin "115") (pinfunction "115_115") (pintype "passive+no_connect"))
    )
    (net (code "128") (name "unconnected-(CN1-Pad116)") (class "Default")
      (node (ref "CN1") (pin "116") (pinfunction "116_116") (pintype "passive+no_connect"))
    )
    (net (code "129") (name "unconnected-(CN1-Pad117)") (class "Default")
      (node (ref "CN1") (pin "117") (pinfunction "117_117") (pintype "passive+no_connect"))
    )
    (net (code "130") (name "unconnected-(CN1-Pad120)") (class "Default")
      (node (ref "CN1") (pin "120") (pinfunction "120_120") (pintype "passive+no_connect"))
    )
    (net (code "131") (name "unconnected-(CN1-Pad121)") (class "Default")
      (node (ref "CN1") (pin "121") (pinfunction "121_121") (pintype "passive+no_connect"))
    )
    (net (code "132") (name "unconnected-(CN1-Pad122)") (class "Default")
      (node (ref "CN1") (pin "122") (pinfunction "122_122") (pintype "passive+no_connect"))
    )
    (net (code "133") (name "unconnected-(CN1-Pad123)") (class "Default")
      (node (ref "CN1") (pin "123") (pinfunction "123_123") (pintype "passive+no_connect"))
    )
    (net (code "134") (name "unconnected-(CN1-Pad127)") (class "Default")
      (node (ref "CN1") (pin "127") (pinfunction "127_127") (pintype "passive+no_connect"))
    )
    (net (code "135") (name "unconnected-(CN1-Pad128)") (class "Default")
      (node (ref "CN1") (pin "128") (pinfunction "128_128") (pintype "passive+no_connect"))
    )
    (net (code "136") (name "unconnected-(CN1-Pad130)") (class "Default")
      (node (ref "CN1") (pin "130") (pinfunction "130_130") (pintype "passive+no_connect"))
    )
    (net (code "137") (name "unconnected-(CN1-Pad131)") (class "Default")
      (node (ref "CN1") (pin "131") (pinfunction "131_131") (pintype "passive+no_connect"))
    )
    (net (code "138") (name "unconnected-(CN1-Pad133)") (class "Default")
      (node (ref "CN1") (pin "133") (pinfunction "133_133") (pintype "passive+no_connect"))
    )
    (net (code "139") (name "unconnected-(CN1-Pad134)") (class "Default")
      (node (ref "CN1") (pin "134") (pinfunction "134_134") (pintype "passive+no_connect"))
    )
    (net (code "140") (name "unconnected-(CN1-Pad136)") (class "Default")
      (node (ref "CN1") (pin "136") (pinfunction "136_136") (pintype "passive+no_connect"))
    )
    (net (code "141") (name "unconnected-(CN1-Pad137)") (class "Default")
      (node (ref "CN1") (pin "137") (pinfunction "137_137") (pintype "passive+no_connect"))
    )
    (net (code "142") (name "unconnected-(CN1-Pad139)") (class "Default")
      (node (ref "CN1") (pin "139") (pinfunction "139_139") (pintype "passive+no_connect"))
    )
    (net (code "143") (name "unconnected-(CN1-Pad140)") (class "Default")
      (node (ref "CN1") (pin "140") (pinfunction "140_140") (pintype "passive+no_connect"))
    )
    (net (code "144") (name "unconnected-(CN1-Pad142)") (class "Default")
      (node (ref "CN1") (pin "142") (pinfunction "142_142") (pintype "passive+no_connect"))
    )
    (net (code "145") (name "unconnected-(CN1-Pad143)") (class "Default")
      (node (ref "CN1") (pin "143") (pinfunction "143_143") (pintype "passive+no_connect"))
    )
    (net (code "146") (name "unconnected-(CN1-Pad145)") (class "Default")
      (node (ref "CN1") (pin "145") (pinfunction "145_145") (pintype "passive+no_connect"))
    )
    (net (code "147") (name "unconnected-(CN1-Pad148)") (class "Default")
      (node (ref "CN1") (pin "148") (pinfunction "148_148") (pintype "passive+no_connect"))
    )
    (net (code "148") (name "unconnected-(CN1-Pad149)") (class "Default")
      (node (ref "CN1") (pin "149") (pinfunction "149_149") (pintype "passive+no_connect"))
    )
    (net (code "149") (name "unconnected-(CN1-Pad150)") (class "Default")
      (node (ref "CN1") (pin "150") (pinfunction "150_150") (pintype "passive+no_connect"))
    )
    (net (code "150") (name "unconnected-(CN1-Pad151)") (class "Default")
      (node (ref "CN1") (pin "151") (pinfunction "151_151") (pintype "passive+no_connect"))
    )
    (net (code "151") (name "unconnected-(CN1-Pad154)") (class "Default")
      (node (ref "CN1") (pin "154") (pinfunction "154_154") (pintype "passive+no_connect"))
    )
    (net (code "152") (name "unconnected-(CN1-Pad155)") (class "Default")
      (node (ref "CN1") (pin "155") (pinfunction "155_155") (pintype "passive+no_connect"))
    )
    (net (code "153") (name "unconnected-(CN1-Pad156)") (class "Default")
      (node (ref "CN1") (pin "156") (pinfunction "156_156") (pintype "passive+no_connect"))
    )
    (net (code "154") (name "unconnected-(CN1-Pad157)") (class "Default")
      (node (ref "CN1") (pin "157") (pinfunction "157_157") (pintype "passive+no_connect"))
    )
    (net (code "155") (name "unconnected-(CN1-Pad160)") (class "Default")
      (node (ref "CN1") (pin "160") (pinfunction "160_160") (pintype "passive+no_connect"))
    )
    (net (code "156") (name "unconnected-(CN1-Pad161)") (class "Default")
      (node (ref "CN1") (pin "161") (pinfunction "161_161") (pintype "passive+no_connect"))
    )
    (net (code "157") (name "unconnected-(CN1-Pad162)") (class "Default")
      (node (ref "CN1") (pin "162") (pinfunction "162_162") (pintype "passive+no_connect"))
    )
    (net (code "158") (name "unconnected-(CN1-Pad163)") (class "Default")
      (node (ref "CN1") (pin "163") (pinfunction "163_163") (pintype "passive+no_connect"))
    )
    (net (code "159") (name "unconnected-(CN1-Pad166)") (class "Default")
      (node (ref "CN1") (pin "166") (pinfunction "166_166") (pintype "passive+no_connect"))
    )
    (net (code "160") (name "unconnected-(CN1-Pad167)") (class "Default")
      (node (ref "CN1") (pin "167") (pinfunction "167_167") (pintype "passive+no_connect"))
    )
    (net (code "161") (name "unconnected-(CN1-Pad168)") (class "Default")
      (node (ref "CN1") (pin "168") (pinfunction "168_168") (pintype "passive+no_connect"))
    )
    (net (code "162") (name "unconnected-(CN1-Pad169)") (class "Default")
      (node (ref "CN1") (pin "169") (pinfunction "169_169") (pintype "passive+no_connect"))
    )
    (net (code "163") (name "unconnected-(CN1-Pad172)") (class "Default")
      (node (ref "CN1") (pin "172") (pinfunction "172_172") (pintype "passive+no_connect"))
    )
    (net (code "164") (name "unconnected-(CN1-Pad173)") (class "Default")
      (node (ref "CN1") (pin "173") (pinfunction "173_173") (pintype "passive+no_connect"))
    )
    (net (code "165") (name "unconnected-(CN1-Pad174)") (class "Default")
      (node (ref "CN1") (pin "174") (pinfunction "174_174") (pintype "passive+no_connect"))
    )
    (net (code "166") (name "unconnected-(CN1-Pad175)") (class "Default")
      (node (ref "CN1") (pin "175") (pinfunction "175_175") (pintype "passive+no_connect"))
    )
    (net (code "167") (name "unconnected-(CN1-Pad178)") (class "Default")
      (node (ref "CN1") (pin "178") (pinfunction "178_178") (pintype "passive+no_connect"))
    )
    (net (code "168") (name "unconnected-(CN1-Pad179)") (class "Default")
      (node (ref "CN1") (pin "179") (pinfunction "179_179") (pintype "passive+no_connect"))
    )
    (net (code "169") (name "unconnected-(CN1-Pad180)") (class "Default")
      (node (ref "CN1") (pin "180") (pinfunction "180_180") (pintype "passive+no_connect"))
    )
    (net (code "170") (name "unconnected-(CN1-Pad181)") (class "Default")
      (node (ref "CN1") (pin "181") (pinfunction "181_181") (pintype "passive+no_connect"))
    )
    (net (code "171") (name "unconnected-(CN1-Pad182)") (class "Default")
      (node (ref "CN1") (pin "182") (pinfunction "182_182") (pintype "passive+no_connect"))
    )
    (net (code "172") (name "unconnected-(CN1-Pad183)") (class "Default")
      (node (ref "CN1") (pin "183") (pinfunction "183_183") (pintype "passive+no_connect"))
    )
    (net (code "173") (name "unconnected-(CN1-Pad184)") (class "Default")
      (node (ref "CN1") (pin "184") (pinfunction "184_184") (pintype "passive+no_connect"))
    )
    (net (code "174") (name "unconnected-(CN1-Pad186)") (class "Default")
      (node (ref "CN1") (pin "186") (pinfunction "186_186") (pintype "passive+no_connect"))
    )
    (net (code "175") (name "unconnected-(CN1-Pad188)") (class "Default")
      (node (ref "CN1") (pin "188") (pinfunction "188_188") (pintype "passive+no_connect"))
    )
    (net (code "176") (name "unconnected-(CN1-Pad190)") (class "Default")
      (node (ref "CN1") (pin "190") (pinfunction "190_190") (pintype "passive+no_connect"))
    )
    (net (code "177") (name "unconnected-(CN1-Pad192)") (class "Default")
      (node (ref "CN1") (pin "192") (pinfunction "192_192") (pintype "passive+no_connect"))
    )
    (net (code "178") (name "unconnected-(CN1-Pad193)") (class "Default")
      (node (ref "CN1") (pin "193") (pinfunction "193_193") (pintype "passive+no_connect"))
    )
    (net (code "179") (name "unconnected-(CN1-Pad194)") (class "Default")
      (node (ref "CN1") (pin "194") (pinfunction "194_194") (pintype "passive+no_connect"))
    )
    (net (code "180") (name "unconnected-(CN1-Pad195)") (class "Default")
      (node (ref "CN1") (pin "195") (pinfunction "195_195") (pintype "passive+no_connect"))
    )
    (net (code "181") (name "unconnected-(CN1-Pad196)") (class "Default")
      (node (ref "CN1") (pin "196") (pinfunction "196_196") (pintype "passive+no_connect"))
    )
    (net (code "182") (name "unconnected-(CN1-Pad197)") (class "Default")
      (node (ref "CN1") (pin "197") (pinfunction "197_197") (pintype "passive+no_connect"))
    )
    (net (code "183") (name "unconnected-(CN1-Pad198)") (class "Default")
      (node (ref "CN1") (pin "198") (pinfunction "198_198") (pintype "passive+no_connect"))
    )
    (net (code "184") (name "unconnected-(CN1-Pad199)") (class "Default")
      (node (ref "CN1") (pin "199") (pinfunction "199_199") (pintype "passive+no_connect"))
    )
    (net (code "185") (name "unconnected-(CN1-Pad202)") (class "Default")
      (node (ref "CN1") (pin "202") (pinfunction "202_202") (pintype "passive+no_connect"))
    )
    (net (code "186") (name "unconnected-(CN1-Pad203)") (class "Default")
      (node (ref "CN1") (pin "203") (pinfunction "203_203") (pintype "passive+no_connect"))
    )
    (net (code "187") (name "unconnected-(CN1-Pad204)") (class "Default")
      (node (ref "CN1") (pin "204") (pinfunction "204_204") (pintype "passive+no_connect"))
    )
    (net (code "188") (name "unconnected-(CN1-Pad205)") (class "Default")
      (node (ref "CN1") (pin "205") (pinfunction "205_205") (pintype "passive+no_connect"))
    )
    (net (code "189") (name "unconnected-(CN1-Pad206)") (class "Default")
      (node (ref "CN1") (pin "206") (pinfunction "206_206") (pintype "passive+no_connect"))
    )
    (net (code "190") (name "unconnected-(CN1-Pad207)") (class "Default")
      (node (ref "CN1") (pin "207") (pinfunction "207_207") (pintype "passive+no_connect"))
    )
    (net (code "191") (name "unconnected-(CN1-Pad208)") (class "Default")
      (node (ref "CN1") (pin "208") (pinfunction "208_208") (pintype "passive+no_connect"))
    )
    (net (code "192") (name "unconnected-(CN1-Pad209)") (class "Default")
      (node (ref "CN1") (pin "209") (pinfunction "209_209") (pintype "passive+no_connect"))
    )
    (net (code "193") (name "unconnected-(CN1-Pad211)") (class "Default")
      (node (ref "CN1") (pin "211") (pinfunction "211_211") (pintype "passive+no_connect"))
    )
    (net (code "194") (name "unconnected-(CN1-Pad212)") (class "Default")
      (node (ref "CN1") (pin "212") (pinfunction "212_212") (pintype "passive+no_connect"))
    )
    (net (code "195") (name "unconnected-(CN1-Pad213)") (class "Default")
      (node (ref "CN1") (pin "213") (pinfunction "213_213") (pintype "passive+no_connect"))
    )
    (net (code "196") (name "unconnected-(CN1-Pad215)") (class "Default")
      (node (ref "CN1") (pin "215") (pinfunction "215_215") (pintype "passive+no_connect"))
    )
    (net (code "197") (name "unconnected-(CN1-Pad216)") (class "Default")
      (node (ref "CN1") (pin "216") (pinfunction "216_216") (pintype "passive+no_connect"))
    )
    (net (code "198") (name "unconnected-(CN1-Pad218)") (class "Default")
      (node (ref "CN1") (pin "218") (pinfunction "218_218") (pintype "passive+no_connect"))
    )
    (net (code "199") (name "unconnected-(CN1-Pad220)") (class "Default")
      (node (ref "CN1") (pin "220") (pinfunction "220_220") (pintype "passive+no_connect"))
    )
    (net (code "200") (name "unconnected-(CN1-Pad222)") (class "Default")
      (node (ref "CN1") (pin "222") (pinfunction "222_222") (pintype "passive+no_connect"))
    )
    (net (code "201") (name "unconnected-(CN1-Pad224)") (class "Default")
      (node (ref "CN1") (pin "224") (pinfunction "224_224") (pintype "passive+no_connect"))
    )
    (net (code "202") (name "unconnected-(CN1-Pad226)") (class "Default")
      (node (ref "CN1") (pin "226") (pinfunction "226_226") (pintype "passive+no_connect"))
    )
    (net (code "203") (name "unconnected-(CN1-Pad228)") (class "Default")
      (node (ref "CN1") (pin "228") (pinfunction "228_228") (pintype "passive+no_connect"))
    )
    (net (code "204") (name "unconnected-(CN1-Pad230)") (class "Default")
      (node (ref "CN1") (pin "230") (pinfunction "230_230") (pintype "passive+no_connect"))
    )
    (net (code "205") (name "unconnected-(CN1-Pad232)") (class "Default")
      (node (ref "CN1") (pin "232") (pinfunction "232_232") (pintype "passive+no_connect"))
    )
    (net (code "206") (name "unconnected-(CN1-Pad233)") (class "Default")
      (node (ref "CN1") (pin "233") (pinfunction "233_233") (pintype "passive+no_connect"))
    )
    (net (code "207") (name "unconnected-(CN1-Pad234)") (class "Default")
      (node (ref "CN1") (pin "234") (pinfunction "234_234") (pintype "passive+no_connect"))
    )
    (net (code "208") (name "unconnected-(CN1-Pad235)") (class "Default")
      (node (ref "CN1") (pin "235") (pinfunction "235_235") (pintype "passive+no_connect"))
    )
    (net (code "209") (name "unconnected-(CN1-Pad236)") (class "Default")
      (node (ref "CN1") (pin "236") (pinfunction "236_236") (pintype "passive+no_connect"))
    )
    (net (code "210") (name "unconnected-(CN1-Pad237)") (class "Default")
      (node (ref "CN1") (pin "237") (pinfunction "237_237") (pintype "passive+no_connect"))
    )
    (net (code "211") (name "unconnected-(CN1-Pad238)") (class "Default")
      (node (ref "CN1") (pin "238") (pinfunction "238_238") (pintype "passive+no_connect"))
    )
    (net (code "212") (name "unconnected-(JB-Pad3)") (class "Default")
      (node (ref "JB") (pin "3") (pinfunction "3_3") (pintype "passive+no_connect"))
    )
    (net (code "213") (name "unconnected-(JB-Pad4)") (class "Default")
      (node (ref "JB") (pin "4") (pinfunction "4_4") (pintype "passive+no_connect"))
    )
    (net (code "214") (name "unconnected-(JB-Pad7)") (class "Default")
      (node (ref "JB") (pin "7") (pinfunction "7_7") (pintype "passive+no_connect"))
    )
    (net (code "215") (name "unconnected-(JB-Pad8)") (class "Default")
      (node (ref "JB") (pin "8") (pinfunction "8_8") (pintype "passive+no_connect"))
    )
    (net (code "216") (name "unconnected-(JC-Pad3)") (class "Default")
      (node (ref "JC") (pin "3") (pinfunction "3_3") (pintype "passive+no_connect"))
    )
    (net (code "217") (name "unconnected-(JC-Pad7)") (class "Default")
      (node (ref "JC") (pin "7") (pinfunction "7_7") (pintype "passive+no_connect"))
    )
  )
)
